# untitled.net
KiCad netlist of a schematic drawn in EAGLE
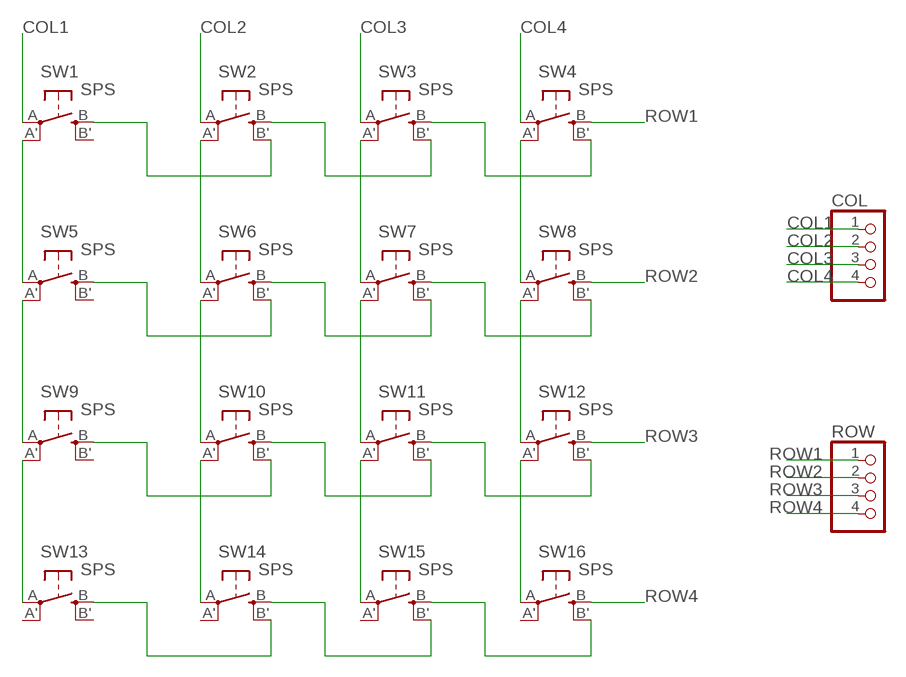
[diagram p0: schematic, sheet 1]

(export (version "E")
  (design (tool "Eeschema 10.0.6"))
  (components
    (comp (ref "COL")
      (value "PINHD-1X4")
      (footprint "eagle-import:1X04")
      (libsource (lib "eagle-import") (part "PINHD-1X4"))
    )
    (comp (ref "ROW")
      (value "PINHD-1X4")
      (footprint "eagle-import:1X04")
      (libsource (lib "eagle-import") (part "PINHD-1X4"))
    )
    (comp (ref "SW1")
      (value "SPS")
      (footprint "eagle-import:EVQ-Q2")
      (libsource (lib "eagle-import") (part "SPST_TACT-EVQQ2"))
    )
    (comp (ref "SW2")
      (value "SPS")
      (footprint "eagle-import:EVQ-Q2")
      (libsource (lib "eagle-import") (part "SPST_TACT-EVQQ2"))
    )
    (comp (ref "SW3")
      (value "SPS")
      (footprint "eagle-import:EVQ-Q2")
      (libsource (lib "eagle-import") (part "SPST_TACT-EVQQ2"))
    )
    (comp (ref "SW4")
      (value "SPS")
      (footprint "eagle-import:EVQ-Q2")
      (libsource (lib "eagle-import") (part "SPST_TACT-EVQQ2"))
    )
    (comp (ref "SW5")
      (value "SPS")
      (footprint "eagle-import:EVQ-Q2")
      (libsource (lib "eagle-import") (part "SPST_TACT-EVQQ2"))
    )
    (comp (ref "SW6")
      (value "SPS")
      (footprint "eagle-import:EVQ-Q2")
      (libsource (lib "eagle-import") (part "SPST_TACT-EVQQ2"))
    )
    (comp (ref "SW7")
      (value "SPS")
      (footprint "eagle-import:EVQ-Q2")
      (libsource (lib "eagle-import") (part "SPST_TACT-EVQQ2"))
    )
    (comp (ref "SW8")
      (value "SPS")
      (footprint "eagle-import:EVQ-Q2")
      (libsource (lib "eagle-import") (part "SPST_TACT-EVQQ2"))
    )
    (comp (ref "SW9")
      (value "SPS")
      (footprint "eagle-import:EVQ-Q2")
      (libsource (lib "eagle-import") (part "SPST_TACT-EVQQ2"))
    )
    (comp (ref "SW10")
      (value "SPS")
      (footprint "eagle-import:EVQ-Q2")
      (libsource (lib "eagle-import") (part "SPST_TACT-EVQQ2"))
    )
    (comp (ref "SW11")
      (value "SPS")
      (footprint "eagle-import:EVQ-Q2")
      (libsource (lib "eagle-import") (part "SPST_TACT-EVQQ2"))
    )
    (comp (ref "SW12")
      (value "SPS")
      (footprint "eagle-import:EVQ-Q2")
      (libsource (lib "eagle-import") (part "SPST_TACT-EVQQ2"))
    )
    (comp (ref "SW13")
      (value "SPS")
      (footprint "eagle-import:EVQ-Q2")
      (libsource (lib "eagle-import") (part "SPST_TACT-EVQQ2"))
    )
    (comp (ref "SW14")
      (value "SPS")
      (footprint "eagle-import:EVQ-Q2")
      (libsource (lib "eagle-import") (part "SPST_TACT-EVQQ2"))
    )
    (comp (ref "SW15")
      (value "SPS")
      (footprint "eagle-import:EVQ-Q2")
      (libsource (lib "eagle-import") (part "SPST_TACT-EVQQ2"))
    )
    (comp (ref "SW16")
      (value "SPS")
      (footprint "eagle-import:EVQ-Q2")
      (libsource (lib "eagle-import") (part "SPST_TACT-EVQQ2"))
    )
  )
  (nets
    (net (code "1") (name "/COL1") (class "Default")
      (node (ref "COL") (pin "1") (pinfunction "1_1") (pintype "passive"))
      (node (ref "SW1") (pin "A") (pinfunction "P_A") (pintype "passive"))
    )
    (net (code "2") (name "/COL2") (class "Default")
      (node (ref "COL") (pin "2") (pinfunction "2_2") (pintype "passive"))
      (node (ref "SW2") (pin "A") (pinfunction "P_A") (pintype "passive"))
    )
    (net (code "3") (name "/COL3") (class "Default")
      (node (ref "COL") (pin "3") (pinfunction "3_3") (pintype "passive"))
      (node (ref "SW3") (pin "A") (pinfunction "P_A") (pintype "passive"))
    )
    (net (code "4") (name "/COL4") (class "Default")
      (node (ref "COL") (pin "4") (pinfunction "4_4") (pintype "passive"))
      (node (ref "SW4") (pin "A") (pinfunction "P_A") (pintype "passive"))
    )
    (net (code "5") (name "/ROW1") (class "Default")
      (node (ref "ROW") (pin "1") (pinfunction "1_1") (pintype "passive"))
      (node (ref "SW4") (pin "B") (pinfunction "S_B") (pintype "passive"))
    )
    (net (code "6") (name "/ROW2") (class "Default")
      (node (ref "ROW") (pin "2") (pinfunction "2_2") (pintype "passive"))
      (node (ref "SW8") (pin "B") (pinfunction "S_B") (pintype "passive"))
    )
    (net (code "7") (name "/ROW3") (class "Default")
      (node (ref "ROW") (pin "3") (pinfunction "3_3") (pintype "passive"))
      (node (ref "SW12") (pin "B") (pinfunction "S_B") (pintype "passive"))
    )
    (net (code "8") (name "/ROW4") (class "Default")
      (node (ref "ROW") (pin "4") (pinfunction "4_4") (pintype "passive"))
      (node (ref "SW16") (pin "B") (pinfunction "S_B") (pintype "passive"))
    )
    (net (code "9") (name "Net-(SW1-P1)") (class "Default")
      (node (ref "SW1") (pin "A'") (pinfunction "P1_A'") (pintype "passive"))
      (node (ref "SW5") (pin "A") (pinfunction "P_A") (pintype "passive"))
    )
    (net (code "10") (name "Net-(SW1-S)") (class "Default")
      (node (ref "SW1") (pin "B") (pinfunction "S_B") (pintype "passive"))
      (node (ref "SW2") (pin "B'") (pinfunction "S1_B'") (pintype "passive"))
    )
    (net (code "11") (name "Net-(SW2-P1)") (class "Default")
      (node (ref "SW2") (pin "A'") (pinfunction "P1_A'") (pintype "passive"))
      (node (ref "SW6") (pin "A") (pinfunction "P_A") (pintype "passive"))
    )
    (net (code "12") (name "Net-(SW2-S)") (class "Default")
      (node (ref "SW2") (pin "B") (pinfunction "S_B") (pintype "passive"))
      (node (ref "SW3") (pin "B'") (pinfunction "S1_B'") (pintype "passive"))
    )
    (net (code "13") (name "Net-(SW3-P1)") (class "Default")
      (node (ref "SW3") (pin "A'") (pinfunction "P1_A'") (pintype "passive"))
      (node (ref "SW7") (pin "A") (pinfunction "P_A") (pintype "passive"))
    )
    (net (code "14") (name "Net-(SW3-S)") (class "Default")
      (node (ref "SW3") (pin "B") (pinfunction "S_B") (pintype "passive"))
      (node (ref "SW4") (pin "B'") (pinfunction "S1_B'") (pintype "passive"))
    )
    (net (code "15") (name "Net-(SW4-P1)") (class "Default")
      (node (ref "SW4") (pin "A'") (pinfunction "P1_A'") (pintype "passive"))
      (node (ref "SW8") (pin "A") (pinfunction "P_A") (pintype "passive"))
    )
    (net (code "16") (name "Net-(SW5-P1)") (class "Default")
      (node (ref "SW5") (pin "A'") (pinfunction "P1_A'") (pintype "passive"))
      (node (ref "SW9") (pin "A") (pinfunction "P_A") (pintype "passive"))
    )
    (net (code "17") (name "Net-(SW5-S)") (class "Default")
      (node (ref "SW5") (pin "B") (pinfunction "S_B") (pintype "passive"))
      (node (ref "SW6") (pin "B'") (pinfunction "S1_B'") (pintype "passive"))
    )
    (net (code "18") (name "Net-(SW6-S)") (class "Default")
      (node (ref "SW6") (pin "B") (pinfunction "S_B") (pintype "passive"))
      (node (ref "SW7") (pin "B'") (pinfunction "S1_B'") (pintype "passive"))
    )
    (net (code "19") (name "Net-(SW7-S)") (class "Default")
      (node (ref "SW7") (pin "B") (pinfunction "S_B") (pintype "passive"))
      (node (ref "SW8") (pin "B'") (pinfunction "S1_B'") (pintype "passive"))
    )
    (net (code "20") (name "Net-(SW10-P)") (class "Default")
      (node (ref "SW10") (pin "A") (pinfunction "P_A") (pintype "passive"))
      (node (ref "SW6") (pin "A'") (pinfunction "P1_A'") (pintype "passive"))
    )
    (net (code "21") (name "Net-(SW10-P1)") (class "Default")
      (node (ref "SW10") (pin "A'") (pinfunction "P1_A'") (pintype "passive"))
      (node (ref "SW14") (pin "A") (pinfunction "P_A") (pintype "passive"))
    )
    (net (code "22") (name "Net-(SW10-S)") (class "Default")
      (node (ref "SW10") (pin "B") (pinfunction "S_B") (pintype "passive"))
      (node (ref "SW11") (pin "B'") (pinfunction "S1_B'") (pintype "passive"))
    )
    (net (code "23") (name "Net-(SW10-S1)") (class "Default")
      (node (ref "SW10") (pin "B'") (pinfunction "S1_B'") (pintype "passive"))
      (node (ref "SW9") (pin "B") (pinfunction "S_B") (pintype "passive"))
    )
    (net (code "24") (name "Net-(SW11-P)") (class "Default")
      (node (ref "SW11") (pin "A") (pinfunction "P_A") (pintype "passive"))
      (node (ref "SW7") (pin "A'") (pinfunction "P1_A'") (pintype "passive"))
    )
    (net (code "25") (name "Net-(SW11-P1)") (class "Default")
      (node (ref "SW11") (pin "A'") (pinfunction "P1_A'") (pintype "passive"))
      (node (ref "SW15") (pin "A") (pinfunction "P_A") (pintype "passive"))
    )
    (net (code "26") (name "Net-(SW11-S)") (class "Default")
      (node (ref "SW11") (pin "B") (pinfunction "S_B") (pintype "passive"))
      (node (ref "SW12") (pin "B'") (pinfunction "S1_B'") (pintype "passive"))
    )
    (net (code "27") (name "Net-(SW12-P)") (class "Default")
      (node (ref "SW12") (pin "A") (pinfunction "P_A") (pintype "passive"))
      (node (ref "SW8") (pin "A'") (pinfunction "P1_A'") (pintype "passive"))
    )
    (net (code "28") (name "Net-(SW12-P1)") (class "Default")
      (node (ref "SW12") (pin "A'") (pinfunction "P1_A'") (pintype "passive"))
      (node (ref "SW16") (pin "A") (pinfunction "P_A") (pintype "passive"))
    )
    (net (code "29") (name "Net-(SW13-P)") (class "Default")
      (node (ref "SW13") (pin "A") (pinfunction "P_A") (pintype "passive"))
      (node (ref "SW9") (pin "A'") (pinfunction "P1_A'") (pintype "passive"))
    )
    (net (code "30") (name "Net-(SW13-S)") (class "Default")
      (node (ref "SW13") (pin "B") (pinfunction "S_B") (pintype "passive"))
      (node (ref "SW14") (pin "B'") (pinfunction "S1_B'") (pintype "passive"))
    )
    (net (code "31") (name "Net-(SW14-S)") (class "Default")
      (node (ref "SW14") (pin "B") (pinfunction "S_B") (pintype "passive"))
      (node (ref "SW15") (pin "B'") (pinfunction "S1_B'") (pintype "passive"))
    )
    (net (code "32") (name "Net-(SW15-S)") (class "Default")
      (node (ref "SW15") (pin "B") (pinfunction "S_B") (pintype "passive"))
      (node (ref "SW16") (pin "B'") (pinfunction "S1_B'") (pintype "passive"))
    )
    (net (code "33") (name "unconnected-(SW1-S1-PadB')") (class "Default")
      (node (ref "SW1") (pin "B'") (pinfunction "S1_B'") (pintype "passive"))
    )
    (net (code "34") (name "unconnected-(SW5-S1-PadB')") (class "Default")
      (node (ref "SW5") (pin "B'") (pinfunction "S1_B'") (pintype "passive"))
    )
    (net (code "35") (name "unconnected-(SW9-S1-PadB')") (class "Default")
      (node (ref "SW9") (pin "B'") (pinfunction "S1_B'") (pintype "passive"))
    )
    (net (code "36") (name "unconnected-(SW13-P1-PadA')") (class "Default")
      (node (ref "SW13") (pin "A'") (pinfunction "P1_A'") (pintype "passive"))
    )
    (net (code "37") (name "unconnected-(SW13-S1-PadB')") (class "Default")
      (node (ref "SW13") (pin "B'") (pinfunction "S1_B'") (pintype "passive"))
    )
    (net (code "38") (name "unconnected-(SW14-P1-PadA')") (class "Default")
      (node (ref "SW14") (pin "A'") (pinfunction "P1_A'") (pintype "passive"))
    )
    (net (code "39") (name "unconnected-(SW15-P1-PadA')") (class "Default")
      (node (ref "SW15") (pin "A'") (pinfunction "P1_A'") (pintype "passive"))
    )
    (net (code "40") (name "unconnected-(SW16-P1-PadA')") (class "Default")
      (node (ref "SW16") (pin "A'") (pinfunction "P1_A'") (pintype "passive"))
    )
  )
)
